# SCH_vs-demon_v1.net
KiCad netlist of a schematic drawn in EasyEDA
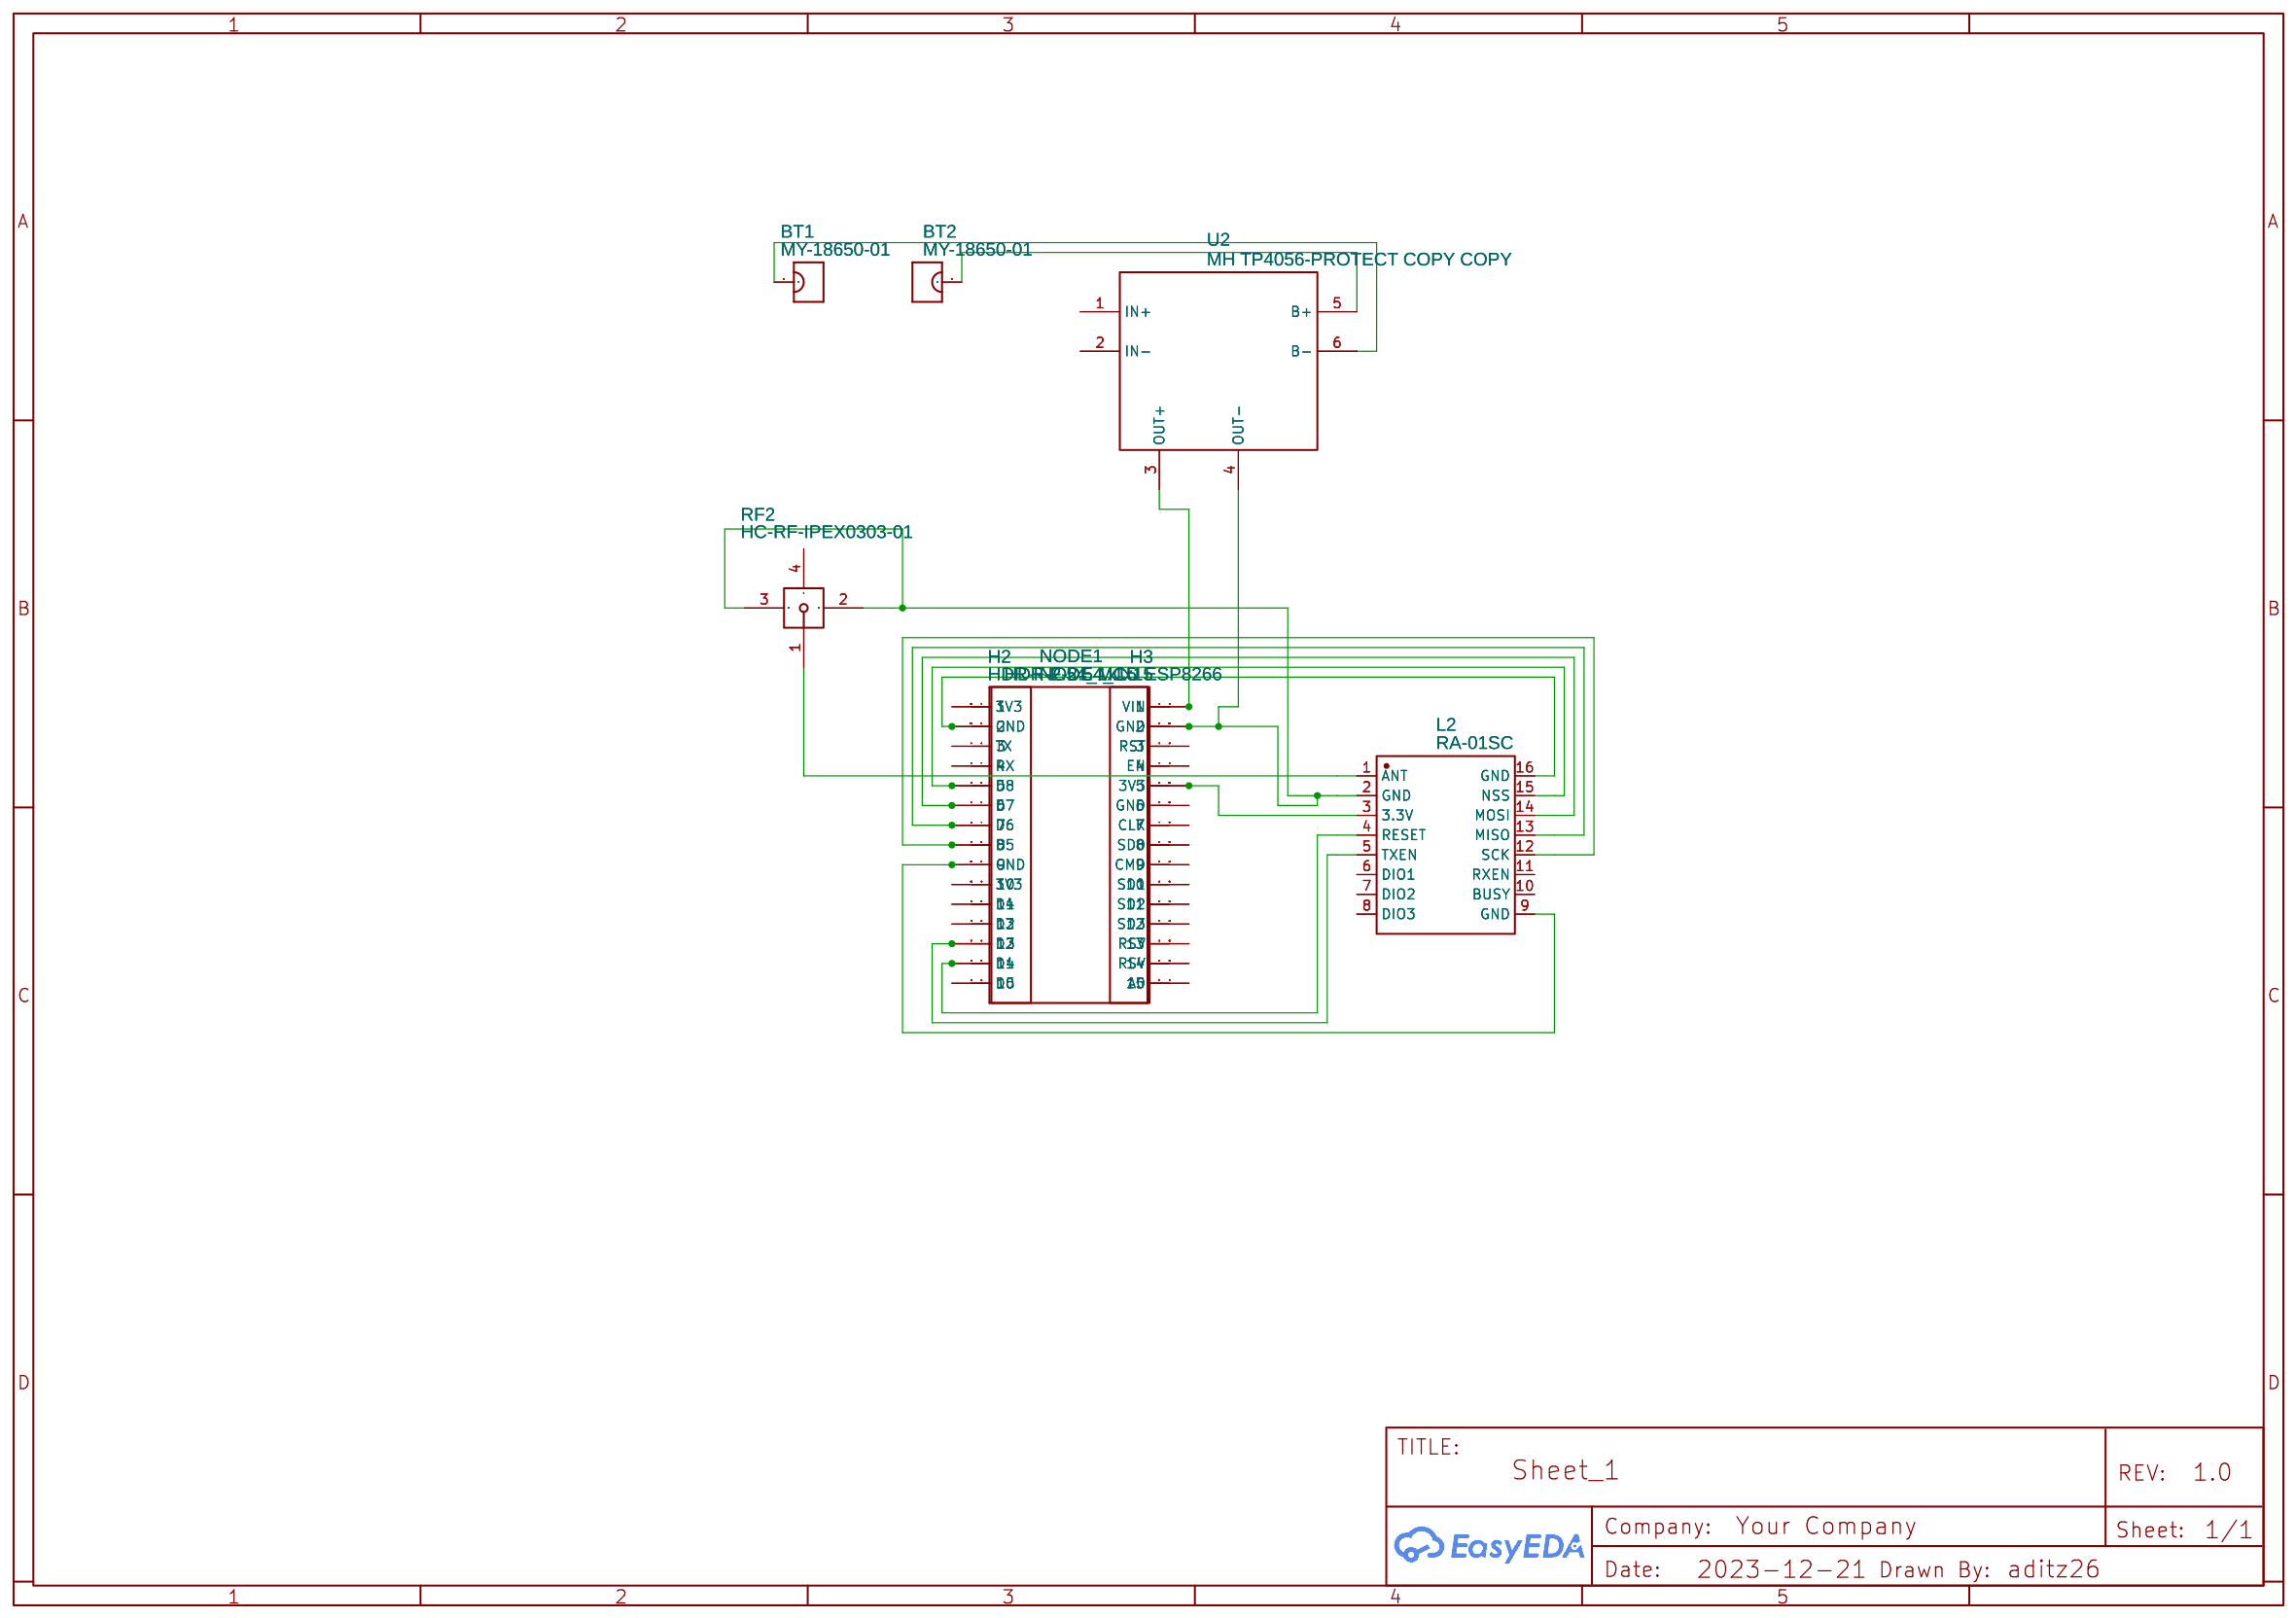
[diagram p0: schematic sheet]

(export (version "E")
  (design (tool "Eeschema 10.0.6"))
  (components
    (comp (ref "BT1")
      (value "MY-18650-01")
      (fields (field (name "Manufacturer") "MYOUNG(美阳)"))
      (libsource (lib "") (part "MY-18650-01_1"))
    )
    (comp (ref "BT2")
      (value "MY-18650-01")
      (fields (field (name "Manufacturer") "MYOUNG(美阳)"))
      (libsource (lib "") (part "MY-18650-01"))
    )
    (comp (ref "H2") (value "HDR-F-2.54_1x15") (libsource (lib "") (part "HDR-F-2.54_1x15")))
    (comp (ref "H3") (value "HDR-F-2.54_1x15") (libsource (lib "") (part "HDR-F-2.54_1x15_1")))
    (comp (ref "L2")
      (value "RA-01SC")
      (fields (field (name "Manufacturer Part") "Ra-01SC") (field (name "Manufacturer") "Ai-Thinker(安信可)"))
      (libsource (lib "") (part "RA-01SC"))
    )
    (comp (ref "NODE1") (value "NODE MCU ESP8266") (libsource (lib "") (part "NODE MCU ESP8266")))
    (comp (ref "RF2")
      (value "HC-RF-IPEX0303-01")
      (fields (field (name "Manufacturer") "HCTL(华灿天禄)"))
      (libsource (lib "") (part "HC-RF-IPEX0303-01"))
    )
    (comp (ref "U2")
      (value "MH TP4056-PROTECT COPY COPY")
      (libsource (lib "") (part "MH TP4056-PROTECT COPY COPY"))
    )
  )
  (nets
    (net (code "1") (name "Net-(H2-Pad2)") (class "Default")
      (node (ref "H2") (pin "2") (pinfunction "2_2") (pintype "unspecified"))
      (node (ref "L2") (pin "16") (pinfunction "GND_16") (pintype "unspecified"))
      (node (ref "NODE1") (pin "GND@1") (pinfunction "GND_GND@1") (pintype "unspecified"))
    )
    (net (code "2") (name "Net-(H2-Pad9)") (class "Default")
      (node (ref "H2") (pin "9") (pinfunction "9_9") (pintype "unspecified"))
      (node (ref "L2") (pin "9") (pinfunction "GND_9") (pintype "unspecified"))
      (node (ref "NODE1") (pin "GND@2") (pinfunction "GND_GND@2") (pintype "unspecified"))
    )
    (net (code "3") (name "Net-(L2-3.3V)") (class "Default")
      (node (ref "H3") (pin "5") (pinfunction "5_5") (pintype "unspecified"))
      (node (ref "L2") (pin "3") (pinfunction "3.3V_3") (pintype "unspecified"))
      (node (ref "NODE1") (pin "3V3@3") (pinfunction "3V3_3V3@3") (pintype "unspecified"))
    )
    (net (code "4") (name "Net-(L2-ANT)") (class "Default")
      (node (ref "L2") (pin "1") (pinfunction "ANT_1") (pintype "unspecified"))
      (node (ref "RF2") (pin "1") (pinfunction "1_1") (pintype "unspecified"))
    )
    (net (code "5") (name "Net-(L2-MISO)") (class "Default")
      (node (ref "H2") (pin "7") (pinfunction "7_7") (pintype "unspecified"))
      (node (ref "L2") (pin "13") (pinfunction "MISO_13") (pintype "unspecified"))
      (node (ref "NODE1") (pin "D6") (pinfunction "D6_D6") (pintype "unspecified"))
    )
    (net (code "6") (name "Net-(L2-MOSI)") (class "Default")
      (node (ref "H2") (pin "6") (pinfunction "6_6") (pintype "unspecified"))
      (node (ref "L2") (pin "14") (pinfunction "MOSI_14") (pintype "unspecified"))
      (node (ref "NODE1") (pin "D7") (pinfunction "D7_D7") (pintype "unspecified"))
    )
    (net (code "7") (name "Net-(L2-NSS)") (class "Default")
      (node (ref "H2") (pin "5") (pinfunction "5_5") (pintype "unspecified"))
      (node (ref "L2") (pin "15") (pinfunction "NSS_15") (pintype "unspecified"))
      (node (ref "NODE1") (pin "D8") (pinfunction "D8_D8") (pintype "unspecified"))
    )
    (net (code "8") (name "Net-(L2-RESET)") (class "Default")
      (node (ref "H2") (pin "14") (pinfunction "14_14") (pintype "unspecified"))
      (node (ref "L2") (pin "4") (pinfunction "RESET_4") (pintype "unspecified"))
      (node (ref "NODE1") (pin "D1") (pinfunction "D1_D1") (pintype "unspecified"))
    )
    (net (code "9") (name "Net-(L2-SCK)") (class "Default")
      (node (ref "H2") (pin "8") (pinfunction "8_8") (pintype "unspecified"))
      (node (ref "L2") (pin "12") (pinfunction "SCK_12") (pintype "unspecified"))
      (node (ref "NODE1") (pin "D5") (pinfunction "D5_D5") (pintype "unspecified"))
    )
    (net (code "10") (name "Net-(L2-TXEN)") (class "Default")
      (node (ref "H2") (pin "13") (pinfunction "13_13") (pintype "unspecified"))
      (node (ref "L2") (pin "5") (pinfunction "TXEN_5") (pintype "unspecified"))
      (node (ref "NODE1") (pin "D2") (pinfunction "D2_D2") (pintype "unspecified"))
    )
    (net (code "11") (name "Net-(U2-B+)") (class "Default")
      (node (ref "BT2") (pin "1") (pinfunction "1_1") (pintype "unspecified"))
      (node (ref "U2") (pin "5") (pinfunction "B+_5") (pintype "unspecified"))
    )
    (net (code "12") (name "Net-(U2-B-)") (class "Default")
      (node (ref "BT1") (pin "1") (pinfunction "1_1") (pintype "unspecified"))
      (node (ref "U2") (pin "6") (pinfunction "B-_6") (pintype "unspecified"))
    )
    (net (code "13") (name "Net-(U2-OUT+)") (class "Default")
      (node (ref "H3") (pin "1") (pinfunction "1_1") (pintype "unspecified"))
      (node (ref "NODE1") (pin "VIN") (pinfunction "VIN_VIN") (pintype "unspecified"))
      (node (ref "U2") (pin "3") (pinfunction "OUT+_3") (pintype "unspecified"))
    )
    (net (code "14") (name "Net-(U2-OUT-)") (class "Default")
      (node (ref "H3") (pin "2") (pinfunction "2_2") (pintype "unspecified"))
      (node (ref "L2") (pin "2") (pinfunction "GND_2") (pintype "unspecified"))
      (node (ref "NODE1") (pin "GND@4") (pinfunction "GND_GND@4") (pintype "unspecified"))
      (node (ref "RF2") (pin "2") (pinfunction "2_2") (pintype "unspecified"))
      (node (ref "RF2") (pin "3") (pinfunction "3_3") (pintype "unspecified"))
      (node (ref "U2") (pin "4") (pinfunction "OUT-_4") (pintype "unspecified"))
    )
    (net (code "15") (name "unconnected-(H2-Pad1)") (class "Default")
      (node (ref "H2") (pin "1") (pinfunction "1_1") (pintype "unspecified"))
    )
    (net (code "16") (name "unconnected-(H2-Pad3)") (class "Default")
      (node (ref "H2") (pin "3") (pinfunction "3_3") (pintype "unspecified"))
    )
    (net (code "17") (name "unconnected-(H2-Pad4)") (class "Default")
      (node (ref "H2") (pin "4") (pinfunction "4_4") (pintype "unspecified"))
    )
    (net (code "18") (name "unconnected-(H2-Pad10)") (class "Default")
      (node (ref "H2") (pin "10") (pinfunction "10_10") (pintype "unspecified"))
    )
    (net (code "19") (name "unconnected-(H2-Pad11)") (class "Default")
      (node (ref "H2") (pin "11") (pinfunction "11_11") (pintype "unspecified"))
    )
    (net (code "20") (name "unconnected-(H2-Pad12)") (class "Default")
      (node (ref "H2") (pin "12") (pinfunction "12_12") (pintype "unspecified"))
    )
    (net (code "21") (name "unconnected-(H2-Pad15)") (class "Default")
      (node (ref "H2") (pin "15") (pinfunction "15_15") (pintype "unspecified"))
    )
    (net (code "22") (name "unconnected-(H3-Pad3)") (class "Default")
      (node (ref "H3") (pin "3") (pinfunction "3_3") (pintype "unspecified"))
    )
    (net (code "23") (name "unconnected-(H3-Pad4)") (class "Default")
      (node (ref "H3") (pin "4") (pinfunction "4_4") (pintype "unspecified"))
    )
    (net (code "24") (name "unconnected-(H3-Pad6)") (class "Default")
      (node (ref "H3") (pin "6") (pinfunction "6_6") (pintype "unspecified"))
    )
    (net (code "25") (name "unconnected-(H3-Pad7)") (class "Default")
      (node (ref "H3") (pin "7") (pinfunction "7_7") (pintype "unspecified"))
    )
    (net (code "26") (name "unconnected-(H3-Pad8)") (class "Default")
      (node (ref "H3") (pin "8") (pinfunction "8_8") (pintype "unspecified"))
    )
    (net (code "27") (name "unconnected-(H3-Pad9)") (class "Default")
      (node (ref "H3") (pin "9") (pinfunction "9_9") (pintype "unspecified"))
    )
    (net (code "28") (name "unconnected-(H3-Pad10)") (class "Default")
      (node (ref "H3") (pin "10") (pinfunction "10_10") (pintype "unspecified"))
    )
    (net (code "29") (name "unconnected-(H3-Pad11)") (class "Default")
      (node (ref "H3") (pin "11") (pinfunction "11_11") (pintype "unspecified"))
    )
    (net (code "30") (name "unconnected-(H3-Pad12)") (class "Default")
      (node (ref "H3") (pin "12") (pinfunction "12_12") (pintype "unspecified"))
    )
    (net (code "31") (name "unconnected-(H3-Pad13)") (class "Default")
      (node (ref "H3") (pin "13") (pinfunction "13_13") (pintype "unspecified"))
    )
    (net (code "32") (name "unconnected-(H3-Pad14)") (class "Default")
      (node (ref "H3") (pin "14") (pinfunction "14_14") (pintype "unspecified"))
    )
    (net (code "33") (name "unconnected-(H3-Pad15)") (class "Default")
      (node (ref "H3") (pin "15") (pinfunction "15_15") (pintype "unspecified"))
    )
    (net (code "34") (name "unconnected-(L2-BUSY-Pad10)") (class "Default")
      (node (ref "L2") (pin "10") (pinfunction "BUSY_10") (pintype "unspecified"))
    )
    (net (code "35") (name "unconnected-(L2-DIO1-Pad6)") (class "Default")
      (node (ref "L2") (pin "6") (pinfunction "DIO1_6") (pintype "unspecified"))
    )
    (net (code "36") (name "unconnected-(L2-DIO2-Pad7)") (class "Default")
      (node (ref "L2") (pin "7") (pinfunction "DIO2_7") (pintype "unspecified"))
    )
    (net (code "37") (name "unconnected-(L2-DIO3-Pad8)") (class "Default")
      (node (ref "L2") (pin "8") (pinfunction "DIO3_8") (pintype "unspecified"))
    )
    (net (code "38") (name "unconnected-(L2-RXEN-Pad11)") (class "Default")
      (node (ref "L2") (pin "11") (pinfunction "RXEN_11") (pintype "unspecified"))
    )
    (net (code "39") (name "unconnected-(NODE1-3V3-Pad3V3@1)") (class "Default")
      (node (ref "NODE1") (pin "3V3@1") (pinfunction "3V3_3V3@1") (pintype "unspecified"))
    )
    (net (code "40") (name "unconnected-(NODE1-3V3-Pad3V3@2)") (class "Default")
      (node (ref "NODE1") (pin "3V3@2") (pinfunction "3V3_3V3@2") (pintype "unspecified"))
    )
    (net (code "41") (name "unconnected-(NODE1-GND-PadGND@3)") (class "Default")
      (node (ref "NODE1") (pin "GND@3") (pinfunction "GND_GND@3") (pintype "unspecified"))
    )
    (net (code "42") (name "unconnected-(NODE1-PadA0)") (class "Default")
      (node (ref "NODE1") (pin "A0") (pinfunction "A0_A0") (pintype "unspecified"))
    )
    (net (code "43") (name "unconnected-(NODE1-PadCLK)") (class "Default")
      (node (ref "NODE1") (pin "CLK") (pinfunction "CLK_CLK") (pintype "unspecified"))
    )
    (net (code "44") (name "unconnected-(NODE1-PadCMD)") (class "Default")
      (node (ref "NODE1") (pin "CMD") (pinfunction "CMD_CMD") (pintype "unspecified"))
    )
    (net (code "45") (name "unconnected-(NODE1-PadD0)") (class "Default")
      (node (ref "NODE1") (pin "D0") (pinfunction "D0_D0") (pintype "unspecified"))
    )
    (net (code "46") (name "unconnected-(NODE1-PadD3)") (class "Default")
      (node (ref "NODE1") (pin "D3") (pinfunction "D3_D3") (pintype "unspecified"))
    )
    (net (code "47") (name "unconnected-(NODE1-PadD4)") (class "Default")
      (node (ref "NODE1") (pin "D4") (pinfunction "D4_D4") (pintype "unspecified"))
    )
    (net (code "48") (name "unconnected-(NODE1-PadEN)") (class "Default")
      (node (ref "NODE1") (pin "EN") (pinfunction "EN_EN") (pintype "unspecified"))
    )
    (net (code "49") (name "unconnected-(NODE1-PadRST)") (class "Default")
      (node (ref "NODE1") (pin "RST") (pinfunction "RST_RST") (pintype "unspecified"))
    )
    (net (code "50") (name "unconnected-(NODE1-PadRX)") (class "Default")
      (node (ref "NODE1") (pin "RX") (pinfunction "RX_RX") (pintype "unspecified"))
    )
    (net (code "51") (name "unconnected-(NODE1-PadSD1)") (class "Default")
      (node (ref "NODE1") (pin "SD1") (pinfunction "SD1_SD1") (pintype "unspecified"))
    )
    (net (code "52") (name "unconnected-(NODE1-PadSD2)") (class "Default")
      (node (ref "NODE1") (pin "SD2") (pinfunction "SD2_SD2") (pintype "unspecified"))
    )
    (net (code "53") (name "unconnected-(NODE1-PadSD3)") (class "Default")
      (node (ref "NODE1") (pin "SD3") (pinfunction "SD3_SD3") (pintype "unspecified"))
    )
    (net (code "54") (name "unconnected-(NODE1-PadTX)") (class "Default")
      (node (ref "NODE1") (pin "TX") (pinfunction "TX_TX") (pintype "unspecified"))
    )
    (net (code "55") (name "unconnected-(NODE1-RSV-PadRSV1)") (class "Default")
      (node (ref "NODE1") (pin "RSV1") (pinfunction "RSV_RSV1") (pintype "unspecified"))
    )
    (net (code "56") (name "unconnected-(NODE1-RSV-PadRSV2)") (class "Default")
      (node (ref "NODE1") (pin "RSV2") (pinfunction "RSV_RSV2") (pintype "unspecified"))
    )
    (net (code "57") (name "unconnected-(NODE1-SD0-PadSDO)") (class "Default")
      (node (ref "NODE1") (pin "SDO") (pinfunction "SD0_SDO") (pintype "unspecified"))
    )
    (net (code "58") (name "unconnected-(RF2-Pad4)") (class "Default")
      (node (ref "RF2") (pin "4") (pinfunction "4_4") (pintype "unspecified"))
    )
    (net (code "59") (name "unconnected-(U2-IN+-Pad1)") (class "Default")
      (node (ref "U2") (pin "1") (pinfunction "IN+_1") (pintype "unspecified"))
    )
    (net (code "60") (name "unconnected-(U2-IN--Pad2)") (class "Default")
      (node (ref "U2") (pin "2") (pinfunction "IN-_2") (pintype "unspecified"))
    )
  )
)
